# PowerConverterSchematic.net
KiCad netlist of a schematic drawn in Altium Designer
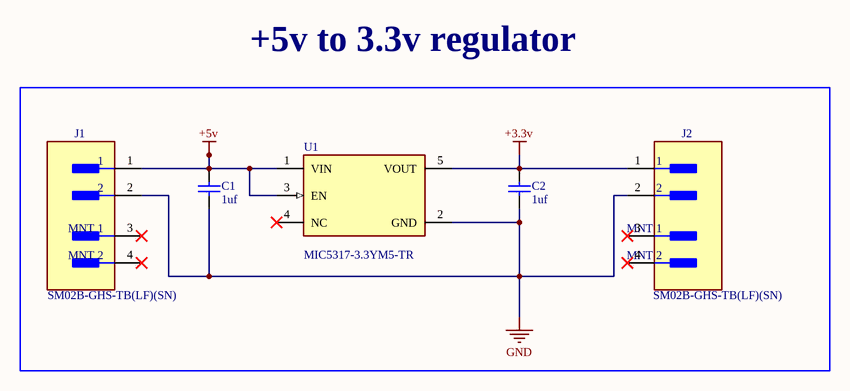
[diagram p0: PowerConverterSchematic.SchDoc]

(export (version "E")
  (design (tool "Eeschema 10.0.6"))
  (components
    (comp (ref "C1")
      (value "1uf")
      (footprint "CAPC2013X145X50NL20T20")
      (fields (field (name "MANUFACTURER") "Vitramon"))
      (libsource (lib "Altium Content Vault") (part "CAP"))
    )
    (comp (ref "C2")
      (value "1uf")
      (footprint "CAPC2013X145X50NL20T20")
      (fields (field (name "MANUFACTURER") "Vitramon"))
      (libsource (lib "Altium Content Vault") (part "CAP"))
    )
    (comp (ref "J1")
      (value "SM02B-GHS-TB(LF)(SN)")
      (footprint "FP-SM02B-GHS-TB_LF_SN-MFG")
      (description "CONN HEADER SMD R/A 2POS 1.25MM")
      (libsource (lib "Altium Content Vault") (part "56ec3178a87b3978bdc1b3682cd516a"))
    )
    (comp (ref "J2")
      (value "SM02B-GHS-TB(LF)(SN)")
      (footprint "FP-SM02B-GHS-TB_LF_SN-MFG")
      (description "CONN HEADER SMD R/A 2POS 1.25MM")
      (libsource (lib "") (part "56ec3178a87b3978bdc1b3682cd516a_1"))
    )
    (comp (ref "U1")
      (value "MIC5317-3.3YM5-TR")
      (footprint "FP-SOT23-5LD-PL-1-MFG")
      (description "IC REG LINEAR 3.3V 150MA SOT23-5")
      (libsource (lib "Altium Content Vault") (part "0a093dae7315cdc977fd108dde87457"))
    )
  )
  (nets
    (net (code "1") (name "+3.3v") (class "Default")
      (node (ref "C2") (pin "2") (pinfunction "2_2") (pintype "passive"))
      (node (ref "J2") (pin "1") (pinfunction "1_1") (pintype "passive"))
      (node (ref "U1") (pin "5") (pinfunction "VOUT_5") (pintype "power_in"))
    )
    (net (code "2") (name "+5v") (class "Default")
      (node (ref "C1") (pin "2") (pinfunction "2_2") (pintype "passive"))
      (node (ref "J1") (pin "1") (pinfunction "1_1") (pintype "passive"))
      (node (ref "U1") (pin "1") (pinfunction "VIN_1") (pintype "power_in"))
      (node (ref "U1") (pin "3") (pinfunction "EN_3") (pintype "input"))
    )
    (net (code "3") (name "GND") (class "Default")
      (node (ref "C1") (pin "1") (pinfunction "1_1") (pintype "passive"))
      (node (ref "C2") (pin "1") (pinfunction "1_1") (pintype "passive"))
      (node (ref "J1") (pin "2") (pinfunction "2_2") (pintype "passive"))
      (node (ref "J2") (pin "2") (pinfunction "2_2") (pintype "passive"))
      (node (ref "U1") (pin "2") (pinfunction "GND_2") (pintype "power_in"))
    )
    (net (code "4") (name "unconnected-(J1-MNT_1-Pad3)") (class "Default")
      (node (ref "J1") (pin "3") (pinfunction "MNT_1_3") (pintype "passive+no_connect"))
    )
    (net (code "5") (name "unconnected-(J1-MNT_2-Pad4)") (class "Default")
      (node (ref "J1") (pin "4") (pinfunction "MNT_2_4") (pintype "passive+no_connect"))
    )
    (net (code "6") (name "unconnected-(J2-MNT_1-Pad3)") (class "Default")
      (node (ref "J2") (pin "3") (pinfunction "MNT_1_3") (pintype "passive+no_connect"))
    )
    (net (code "7") (name "unconnected-(J2-MNT_2-Pad4)") (class "Default")
      (node (ref "J2") (pin "4") (pinfunction "MNT_2_4") (pintype "passive+no_connect"))
    )
    (net (code "8") (name "unconnected-(U1-NC-Pad4)") (class "Default")
      (node (ref "U1") (pin "4") (pinfunction "NC_4") (pintype "passive+no_connect"))
    )
  )
)
